# ISL6236A_DEMO.net
KiCad netlist of a schematic drawn in Altium Designer
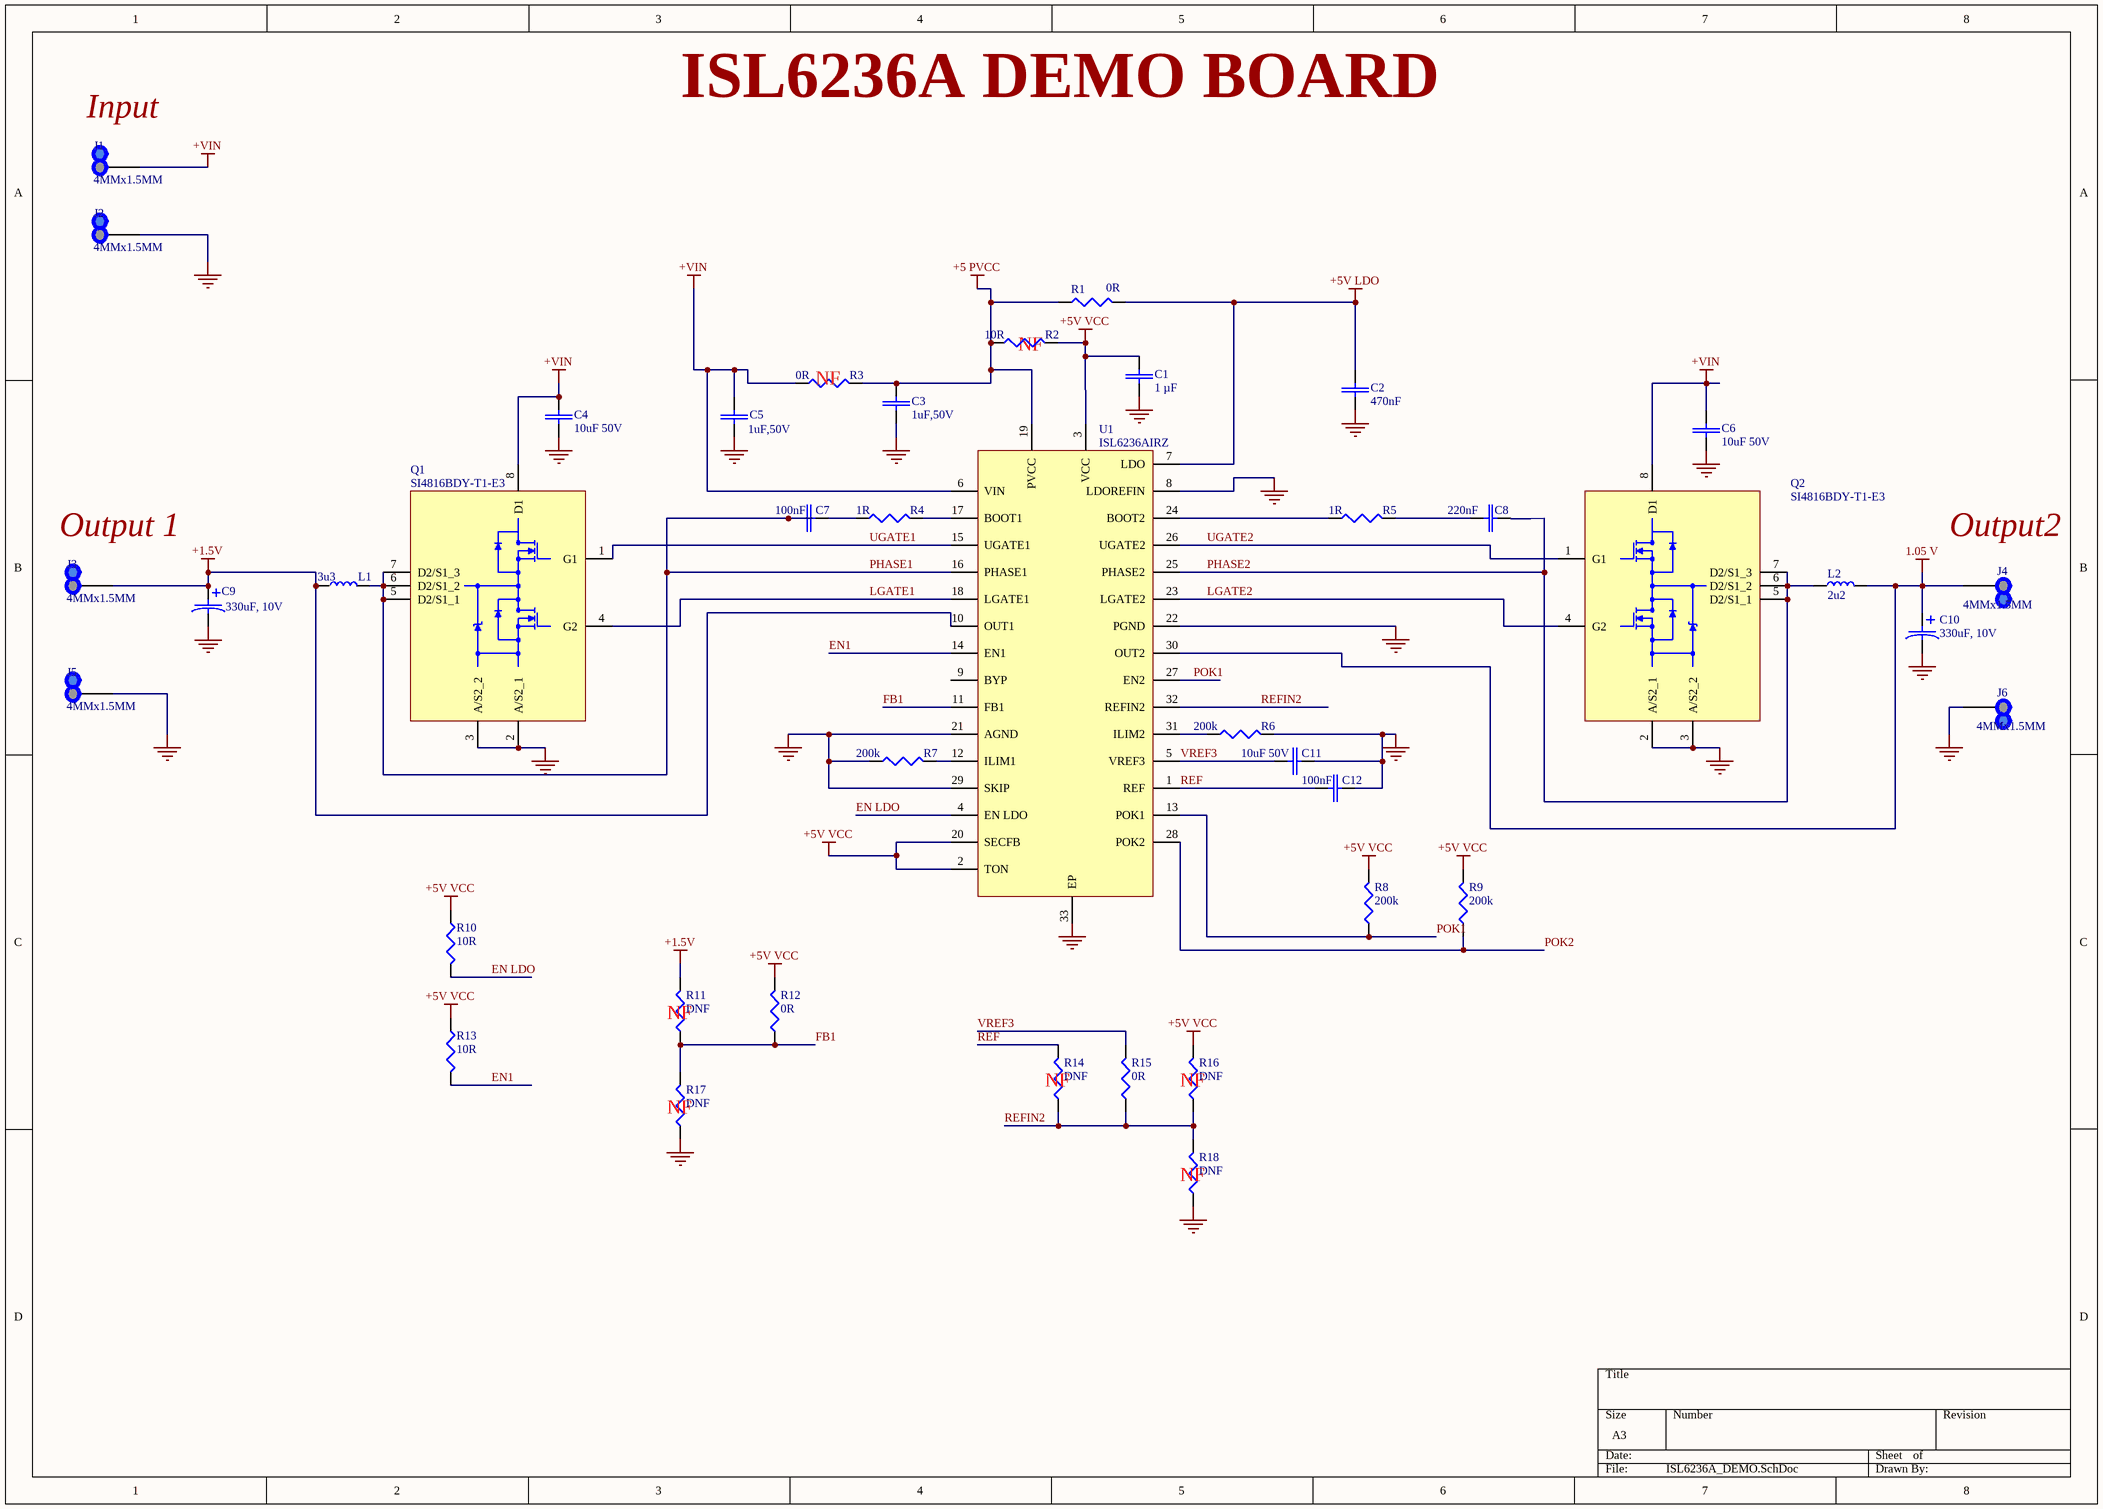
[diagram p0: ISL6236A_DEMO.SchDoc]

(export (version "E")
  (design (tool "Eeschema 10.0.6"))
  (components
    (comp (ref "C1")
      (value "1 µF")
      (footprint "C0805")
      (fields
        (field (name "TOLERANCE") "10%")
        (field (name "VOLTAGE") "25V")
        (field (name "MANUFACTURER") "Kyocera AVX")
      )
      (libsource (lib "ISL6236A_DEMO") (part "08053D105KAT2A"))
    )
    (comp (ref "C2")
      (value "470nF")
      (footprint "C1206")
      (description "Cap Ceramic 4.7uF 10V X5R 10% SMD 1206 85C T/R")
      (fields (field (name "TOLERANCE") "10%") (field (name "MANUFACTURER") "Taiyo Yuden"))
      (libsource (lib "ISL6236A_DEMO") (part "LMK316BJ475KD-T"))
    )
    (comp (ref "C3")
      (value "1uF,50V")
      (footprint "C0805")
      (fields
        (field (name "TOLERANCE") "10%")
        (field (name "MANUFACTURER") "TDK")
        (field (name "MANUFACTURER PART NUMBER") "C2012X7R1H105K125AB")
      )
      (libsource (lib "ISL6236A_DEMO") (part "C2012X7R1H105K125AB"))
    )
    (comp (ref "C4")
      (value "10uF 50V")
      (footprint "C1210")
      (description "CAP CER 10UF 50V X5R 1210")
      (fields (field (name "TOLERANCE") "20%") (field (name "MANUFACTURER") "Taiyo Yuden"))
      (libsource (lib "ISL6236A_DEMO") (part "UMK325BJ106MMHP"))
    )
    (comp (ref "C5")
      (value "1uF,50V")
      (footprint "C0805")
      (fields
        (field (name "TOLERANCE") "10%")
        (field (name "MANUFACTURER") "TDK")
        (field (name "MANUFACTURER PART NUMBER") "C2012X7R1H105K125AB")
      )
      (libsource (lib "ISL6236A_DEMO") (part "C2012X7R1H105K125AB"))
    )
    (comp (ref "C6")
      (value "10uF 50V")
      (footprint "C1210")
      (description "CAP CER 10UF 50V X5R 1210")
      (fields (field (name "TOLERANCE") "20%") (field (name "MANUFACTURER") "Taiyo Yuden"))
      (libsource (lib "ISL6236A_DEMO") (part "UMK325BJ106MMHP"))
    )
    (comp (ref "C7")
      (value "100nF")
      (footprint "C0805")
      (fields
        (field (name "TOLERANCE") "10%")
        (field (name "VOLTAGE") "50V")
        (field (name "MANUFACTURER") "Kyocera AVX")
      )
      (libsource (lib "ISL6236A_DEMO") (part "08055C104KAT4A"))
    )
    (comp (ref "C8")
      (value "220nF")
      (footprint "C0805")
      (description "TAIYO YUDEN - UMK212B7224KG-T - CERAMIC CAPACITOR 0.22UF, 50V, X7R, 10%, 0805, FULL REEL")
      (fields (field (name "TOLERANCE") "10%") (field (name "VOLTAGE") "50V"))
      (libsource (lib "ISL6236A_DEMO") (part "UMK212B7224KG-T"))
    )
    (comp (ref "C9")
      (value "330uF, 10V")
      (footprint "C7343-43")
      (description "Tantalum Capacitors - Polymer SMD 330uF 10volts 20%")
      (fields (field (name "TOLERANCE") "20%") (field (name "VOLTAGE") "10V"))
      (libsource (lib "ISL6236A_DEMO") (part "T530X337M010ATE004"))
    )
    (comp (ref "C10")
      (value "330uF, 10V")
      (footprint "C7343-43")
      (description "Tantalum Capacitors - Polymer SMD 330uF 10volts 20%")
      (fields (field (name "TOLERANCE") "20%") (field (name "VOLTAGE") "10V"))
      (libsource (lib "ISL6236A_DEMO") (part "T530X337M010ATE004"))
    )
    (comp (ref "C11")
      (value "10uF 50V")
      (footprint "C1210")
      (description "CAP CER 10UF 50V X5R 1210")
      (fields (field (name "TOLERANCE") "20%") (field (name "MANUFACTURER") "Taiyo Yuden"))
      (libsource (lib "ISL6236A_DEMO") (part "UMK325BJ106MMHP"))
    )
    (comp (ref "C12")
      (value "100nF")
      (footprint "C0805")
      (fields
        (field (name "TOLERANCE") "10%")
        (field (name "VOLTAGE") "50V")
        (field (name "MANUFACTURER") "Kyocera AVX")
      )
      (libsource (lib "ISL6236A_DEMO") (part "08055C104KAT4A"))
    )
    (comp (ref "J1")
      (value "4MMx1.5MM")
      (footprint "PAD_WITH_HOLE_4MM_1.5MM")
      (description "Pad with a hole 4mm x 1.5mm")
      (libsource (lib "ISL6236A_DEMO") (part "PAD_WITH_HOLE_4MMx1.5MM"))
    )
    (comp (ref "J2")
      (value "4MMx1.5MM")
      (footprint "PAD_WITH_HOLE_4MM_1.5MM")
      (description "Pad with a hole 4mm x 1.5mm")
      (libsource (lib "ISL6236A_DEMO") (part "PAD_WITH_HOLE_4MMx1.5MM"))
    )
    (comp (ref "J3")
      (value "4MMx1.5MM")
      (footprint "PAD_WITH_HOLE_4MM_1.5MM")
      (description "Pad with a hole 4mm x 1.5mm")
      (libsource (lib "ISL6236A_DEMO") (part "PAD_WITH_HOLE_4MMx1.5MM"))
    )
    (comp (ref "J4")
      (value "4MMx1.5MM")
      (footprint "PAD_WITH_HOLE_4MM_1.5MM")
      (description "Pad with a hole 4mm x 1.5mm")
      (libsource (lib "") (part "PAD_WITH_HOLE_4MMx1.5MM_1"))
    )
    (comp (ref "J5")
      (value "4MMx1.5MM")
      (footprint "PAD_WITH_HOLE_4MM_1.5MM")
      (description "Pad with a hole 4mm x 1.5mm")
      (libsource (lib "ISL6236A_DEMO") (part "PAD_WITH_HOLE_4MMx1.5MM"))
    )
    (comp (ref "J6")
      (value "4MMx1.5MM")
      (footprint "PAD_WITH_HOLE_4MM_1.5MM")
      (description "Pad with a hole 4mm x 1.5mm")
      (libsource (lib "") (part "PAD_WITH_HOLE_4MMx1.5MM_1"))
    )
    (comp (ref "L1")
      (value "3u3")
      (footprint "Inductor 744313330")
      (description "WURTH ELEKTRONIK - 744313330 - INDUCTOR, HIGH CURRENT 2.45UH, SMD")
      (fields (field (name "TOLERANCE") "20%") (field (name "MANUFACTURER") "Wurth Electronics"))
      (libsource (lib "ISL6236A_DEMO") (part "744313330"))
    )
    (comp (ref "L2")
      (value "2u2")
      (footprint "Inductor PCC-M1040M-LP")
      (description "Power Choke Shielded Wirewound 2.2uH 20% 100KHz Metal 14.8A 0.00748Ohm DCR Automotive T/R")
      (fields
        (field (name "MANUFACTURER") "Panasonic")
        (field (name "MANUFACTURER PART NUMBER") "ETQP4M2R2KVC")
      )
      (libsource (lib "ISL6236A_DEMO") (part "ETQP4M2R2KVC"))
    )
    (comp (ref "Q1")
      (value "SI4816BDY-T1-E3")
      (footprint "SO-8")
      (description "MOSFET 2N-CH 30V 5.8A 8-SOIC")
      (fields (field (name "MANUFACTURER") "Vishay Siliconix"))
      (libsource (lib "ISL6236A_DEMO") (part "SI4816BDY-T1-E3"))
    )
    (comp (ref "Q2")
      (value "SI4816BDY-T1-E3")
      (footprint "SO-8")
      (description "MOSFET 2N-CH 30V 5.8A 8-SOIC")
      (fields (field (name "MANUFACTURER") "Vishay Siliconix"))
      (libsource (lib "ISL6236A_DEMO") (part "SI4816BDY-T1-E3"))
    )
    (comp (ref "R1")
      (value "0R")
      (footprint "R0805")
      (fields
        (field (name "MANUFACTURER") "Stackpole Electronics")
        (field (name "MANUFACTURER PART NUMBER") "RMCF0805ZT0R00")
      )
      (libsource (lib "ISL6236A_DEMO") (part "RMCF0805ZT0R00"))
    )
    (comp (ref "R2")
      (value "10R")
      (footprint "R0805")
      (description "Res Thin Film 0805 10 Ohm 0.05% 1/10W 10ppm/C Molded SMD SMD Paper T/R")
      (fields (field (name "TOLERANCE") "0.05%") (field (name "MANUFACTURER") "Stackpole Electronics"))
      (libsource (lib "ISL6236A_DEMO") (part "RNCF0805AKT10R0"))
    )
    (comp (ref "R3")
      (value "0R")
      (footprint "R0805")
      (fields
        (field (name "MANUFACTURER") "Stackpole Electronics")
        (field (name "MANUFACTURER PART NUMBER") "RMCF0805ZT0R00")
      )
      (libsource (lib "ISL6236A_DEMO") (part "RMCF0805ZT0R00"))
    )
    (comp (ref "R4")
      (value "1R")
      (footprint "C0805")
      (fields
        (field (name "TOLERANCE") "1%")
        (field (name "MANUFACTURER") "Panasonic")
        (field (name "MANUFACTURER PART NUMBER") "ERJ-6RQF1R0V")
      )
      (libsource (lib "ISL6236A_DEMO") (part "ERJ-6RQF1R0V"))
    )
    (comp (ref "R5")
      (value "1R")
      (footprint "C0805")
      (fields
        (field (name "TOLERANCE") "1%")
        (field (name "MANUFACTURER") "Panasonic")
        (field (name "MANUFACTURER PART NUMBER") "ERJ-6RQF1R0V")
      )
      (libsource (lib "ISL6236A_DEMO") (part "ERJ-6RQF1R0V"))
    )
    (comp (ref "R6")
      (value "200k")
      (footprint "R0805")
      (fields
        (field (name "TOLERANCE") "1%")
        (field (name "MANUFACTURER") "Panasonic")
        (field (name "MANUFACTURER PART NUMBER") "ERJ-6ENF2003V")
      )
      (libsource (lib "ISL6236A_DEMO") (part "ERJ-6ENF2003V"))
    )
    (comp (ref "R7")
      (value "200k")
      (footprint "R0805")
      (fields
        (field (name "TOLERANCE") "1%")
        (field (name "MANUFACTURER") "Panasonic")
        (field (name "MANUFACTURER PART NUMBER") "ERJ-6ENF2003V")
      )
      (libsource (lib "ISL6236A_DEMO") (part "ERJ-6ENF2003V"))
    )
    (comp (ref "R8")
      (value "200k")
      (footprint "R0805")
      (fields
        (field (name "TOLERANCE") "1%")
        (field (name "MANUFACTURER") "Panasonic")
        (field (name "MANUFACTURER PART NUMBER") "ERJ-6ENF2003V")
      )
      (libsource (lib "ISL6236A_DEMO") (part "ERJ-6ENF2003V"))
    )
    (comp (ref "R9")
      (value "200k")
      (footprint "R0805")
      (fields
        (field (name "TOLERANCE") "1%")
        (field (name "MANUFACTURER") "Panasonic")
        (field (name "MANUFACTURER PART NUMBER") "ERJ-6ENF2003V")
      )
      (libsource (lib "ISL6236A_DEMO") (part "ERJ-6ENF2003V"))
    )
    (comp (ref "R10")
      (value "10R")
      (footprint "R0805")
      (description "Res Thin Film 0805 10 Ohm 0.05% 1/10W 10ppm/C Molded SMD SMD Paper T/R")
      (fields (field (name "TOLERANCE") "0.05%") (field (name "MANUFACTURER") "Stackpole Electronics"))
      (libsource (lib "ISL6236A_DEMO") (part "RNCF0805AKT10R0"))
    )
    (comp (ref "R11") (value "DNF") (footprint "R0805") (libsource (lib "ISL6236A_DEMO") (part "RES")))
    (comp (ref "R12")
      (value "0R")
      (footprint "R0805")
      (fields
        (field (name "MANUFACTURER") "Stackpole Electronics")
        (field (name "MANUFACTURER PART NUMBER") "RMCF0805ZT0R00")
      )
      (libsource (lib "ISL6236A_DEMO") (part "RMCF0805ZT0R00"))
    )
    (comp (ref "R13")
      (value "10R")
      (footprint "R0805")
      (description "Res Thin Film 0805 10 Ohm 0.05% 1/10W 10ppm/C Molded SMD SMD Paper T/R")
      (fields (field (name "TOLERANCE") "0.05%") (field (name "MANUFACTURER") "Stackpole Electronics"))
      (libsource (lib "ISL6236A_DEMO") (part "RNCF0805AKT10R0"))
    )
    (comp (ref "R14") (value "DNF") (footprint "R0805") (libsource (lib "ISL6236A_DEMO") (part "RES")))
    (comp (ref "R15")
      (value "0R")
      (footprint "R0805")
      (fields
        (field (name "MANUFACTURER") "Stackpole Electronics")
        (field (name "MANUFACTURER PART NUMBER") "RMCF0805ZT0R00")
      )
      (libsource (lib "ISL6236A_DEMO") (part "RMCF0805ZT0R00"))
    )
    (comp (ref "R16") (value "DNF") (footprint "R0805") (libsource (lib "ISL6236A_DEMO") (part "RES")))
    (comp (ref "R17") (value "DNF") (footprint "R0805") (libsource (lib "ISL6236A_DEMO") (part "RES")))
    (comp (ref "R18") (value "DNF") (footprint "R0805") (libsource (lib "ISL6236A_DEMO") (part "RES")))
    (comp (ref "U1")
      (value "ISL6236AIRZ")
      (footprint "ISL5236A L32.5X5B - duplicate")
      (description "IC MAIN PWR CTRLR QUAD 32-QFN")
      (fields (field (name "MANUFACTURER") "Intersil"))
      (libsource (lib "ISL6236A_DEMO") (part "ISL6236AIRZ"))
    )
  )
  (nets
    (net (code "1") (name "+1.5V") (class "Default")
      (node (ref "C9") (pin "1") (pinfunction "1_1") (pintype "passive"))
      (node (ref "J3") (pin "1") (pinfunction "1_1") (pintype "passive"))
      (node (ref "L1") (pin "1") (pinfunction "1_1") (pintype "passive"))
      (node (ref "R11") (pin "2") (pinfunction "2_2") (pintype "passive"))
      (node (ref "U1") (pin "10") (pinfunction "OUT1_10") (pintype "passive"))
    )
    (net (code "2") (name "+5 PVCC") (class "Default")
      (node (ref "C3") (pin "2") (pinfunction "2_2") (pintype "passive"))
      (node (ref "R1") (pin "1") (pinfunction "1_1") (pintype "passive"))
      (node (ref "R2") (pin "1") (pinfunction "1_1") (pintype "passive"))
      (node (ref "R3") (pin "2") (pinfunction "2_2") (pintype "passive"))
      (node (ref "U1") (pin "19") (pinfunction "PVCC_19") (pintype "passive"))
    )
    (net (code "3") (name "+5V LDO") (class "Default")
      (node (ref "C2") (pin "2") (pinfunction "2_2") (pintype "passive"))
      (node (ref "R1") (pin "2") (pinfunction "2_2") (pintype "passive"))
      (node (ref "U1") (pin "7") (pinfunction "LDO_7") (pintype "passive"))
    )
    (net (code "4") (name "+5V VCC") (class "Default")
      (node (ref "C1") (pin "2") (pinfunction "2_2") (pintype "passive"))
      (node (ref "R10") (pin "1") (pinfunction "1_1") (pintype "passive"))
      (node (ref "R12") (pin "2") (pinfunction "2_2") (pintype "passive"))
      (node (ref "R13") (pin "1") (pinfunction "1_1") (pintype "passive"))
      (node (ref "R16") (pin "2") (pinfunction "2_2") (pintype "passive"))
      (node (ref "R2") (pin "2") (pinfunction "2_2") (pintype "passive"))
      (node (ref "R8") (pin "2") (pinfunction "2_2") (pintype "passive"))
      (node (ref "R9") (pin "2") (pinfunction "2_2") (pintype "passive"))
      (node (ref "U1") (pin "2") (pinfunction "TON_2") (pintype "passive"))
      (node (ref "U1") (pin "20") (pinfunction "SECFB_20") (pintype "passive"))
      (node (ref "U1") (pin "3") (pinfunction "VCC_3") (pintype "passive"))
    )
    (net (code "5") (name "+VIN") (class "Default")
      (node (ref "C4") (pin "2") (pinfunction "2_2") (pintype "passive"))
      (node (ref "C5") (pin "2") (pinfunction "2_2") (pintype "passive"))
      (node (ref "C6") (pin "2") (pinfunction "2_2") (pintype "passive"))
      (node (ref "J1") (pin "1") (pinfunction "1_1") (pintype "passive"))
      (node (ref "Q1") (pin "8") (pinfunction "D1_8") (pintype "passive"))
      (node (ref "Q2") (pin "8") (pinfunction "D1_8") (pintype "passive"))
      (node (ref "R3") (pin "1") (pinfunction "1_1") (pintype "passive"))
      (node (ref "U1") (pin "6") (pinfunction "VIN_6") (pintype "passive"))
    )
    (net (code "6") (name "/EN LDO") (class "Default")
      (node (ref "R10") (pin "2") (pinfunction "2_2") (pintype "passive"))
      (node (ref "U1") (pin "4") (pinfunction "EN_LDO_4") (pintype "passive"))
    )
    (net (code "7") (name "/EN1") (class "Default")
      (node (ref "R13") (pin "2") (pinfunction "2_2") (pintype "passive"))
      (node (ref "U1") (pin "14") (pinfunction "EN1_14") (pintype "passive"))
    )
    (net (code "8") (name "/FB1") (class "Default")
      (node (ref "R11") (pin "1") (pinfunction "1_1") (pintype "passive"))
      (node (ref "R12") (pin "1") (pinfunction "1_1") (pintype "passive"))
      (node (ref "R17") (pin "2") (pinfunction "2_2") (pintype "passive"))
      (node (ref "U1") (pin "11") (pinfunction "FB1_11") (pintype "passive"))
    )
    (net (code "9") (name "/LGATE1") (class "Default")
      (node (ref "Q1") (pin "4") (pinfunction "G2_4") (pintype "passive"))
      (node (ref "U1") (pin "18") (pinfunction "LGATE1_18") (pintype "passive"))
    )
    (net (code "10") (name "/LGATE2") (class "Default")
      (node (ref "Q2") (pin "4") (pinfunction "G2_4") (pintype "passive"))
      (node (ref "U1") (pin "23") (pinfunction "LGATE2_23") (pintype "passive"))
    )
    (net (code "11") (name "/PHASE1") (class "Default")
      (node (ref "C7") (pin "1") (pinfunction "1_1") (pintype "passive"))
      (node (ref "L1") (pin "2") (pinfunction "2_2") (pintype "passive"))
      (node (ref "Q1") (pin "5") (pinfunction "D2/S1_1_5") (pintype "passive"))
      (node (ref "Q1") (pin "6") (pinfunction "D2/S1_2_6") (pintype "passive"))
      (node (ref "Q1") (pin "7") (pinfunction "D2/S1_3_7") (pintype "passive"))
      (node (ref "U1") (pin "16") (pinfunction "PHASE1_16") (pintype "passive"))
    )
    (net (code "12") (name "/PHASE2") (class "Default")
      (node (ref "C8") (pin "2") (pinfunction "2_2") (pintype "passive"))
      (node (ref "L2") (pin "1") (pinfunction "1_1") (pintype "passive"))
      (node (ref "Q2") (pin "5") (pinfunction "D2/S1_1_5") (pintype "passive"))
      (node (ref "Q2") (pin "6") (pinfunction "D2/S1_2_6") (pintype "passive"))
      (node (ref "Q2") (pin "7") (pinfunction "D2/S1_3_7") (pintype "passive"))
      (node (ref "U1") (pin "25") (pinfunction "PHASE2_25") (pintype "passive"))
    )
    (net (code "13") (name "/POK1") (class "Default")
      (node (ref "R8") (pin "1") (pinfunction "1_1") (pintype "passive"))
      (node (ref "U1") (pin "13") (pinfunction "POK1_13") (pintype "passive"))
      (node (ref "U1") (pin "27") (pinfunction "EN2_27") (pintype "passive"))
    )
    (net (code "14") (name "/POK2") (class "Default")
      (node (ref "R9") (pin "1") (pinfunction "1_1") (pintype "passive"))
      (node (ref "U1") (pin "28") (pinfunction "POK2_28") (pintype "passive"))
    )
    (net (code "15") (name "/REF") (class "Default")
      (node (ref "C12") (pin "1") (pinfunction "1_1") (pintype "passive"))
      (node (ref "R14") (pin "2") (pinfunction "2_2") (pintype "passive"))
      (node (ref "U1") (pin "1") (pinfunction "REF_1") (pintype "passive"))
    )
    (net (code "16") (name "/REFIN2") (class "Default")
      (node (ref "R14") (pin "1") (pinfunction "1_1") (pintype "passive"))
      (node (ref "R15") (pin "1") (pinfunction "1_1") (pintype "passive"))
      (node (ref "R16") (pin "1") (pinfunction "1_1") (pintype "passive"))
      (node (ref "R18") (pin "2") (pinfunction "2_2") (pintype "passive"))
      (node (ref "U1") (pin "32") (pinfunction "REFIN2_32") (pintype "passive"))
    )
    (net (code "17") (name "/UGATE1") (class "Default")
      (node (ref "Q1") (pin "1") (pinfunction "G1_1") (pintype "passive"))
      (node (ref "U1") (pin "15") (pinfunction "UGATE1_15") (pintype "passive"))
    )
    (net (code "18") (name "/UGATE2") (class "Default")
      (node (ref "Q2") (pin "1") (pinfunction "G1_1") (pintype "passive"))
      (node (ref "U1") (pin "26") (pinfunction "UGATE2_26") (pintype "passive"))
    )
    (net (code "19") (name "/VREF3") (class "Default")
      (node (ref "C11") (pin "1") (pinfunction "1_1") (pintype "passive"))
      (node (ref "R15") (pin "2") (pinfunction "2_2") (pintype "passive"))
      (node (ref "U1") (pin "5") (pinfunction "VREF3_5") (pintype "passive"))
    )
    (net (code "20") (name "1.05 V") (class "Default")
      (node (ref "C10") (pin "1") (pinfunction "1_1") (pintype "passive"))
      (node (ref "J4") (pin "1") (pinfunction "1_1") (pintype "passive"))
      (node (ref "L2") (pin "2") (pinfunction "2_2") (pintype "passive"))
      (node (ref "U1") (pin "30") (pinfunction "OUT2_30") (pintype "passive"))
    )
    (net (code "21") (name "GND") (class "Default")
      (node (ref "C1") (pin "1") (pinfunction "1_1") (pintype "passive"))
      (node (ref "C10") (pin "2") (pinfunction "2_2") (pintype "passive"))
      (node (ref "C11") (pin "2") (pinfunction "2_2") (pintype "passive"))
      (node (ref "C12") (pin "2") (pinfunction "2_2") (pintype "passive"))
      (node (ref "C2") (pin "1") (pinfunction "1_1") (pintype "passive"))
      (node (ref "C3") (pin "1") (pinfunction "1_1") (pintype "passive"))
      (node (ref "C4") (pin "1") (pinfunction "1_1") (pintype "passive"))
      (node (ref "C5") (pin "1") (pinfunction "1_1") (pintype "passive"))
      (node (ref "C6") (pin "1") (pinfunction "1_1") (pintype "passive"))
      (node (ref "C9") (pin "2") (pinfunction "2_2") (pintype "passive"))
      (node (ref "J2") (pin "1") (pinfunction "1_1") (pintype "passive"))
      (node (ref "J5") (pin "1") (pinfunction "1_1") (pintype "passive"))
      (node (ref "J6") (pin "1") (pinfunction "1_1") (pintype "passive"))
      (node (ref "Q1") (pin "2") (pinfunction "A/S2_1_2") (pintype "passive"))
      (node (ref "Q1") (pin "3") (pinfunction "A/S2_2_3") (pintype "passive"))
      (node (ref "Q2") (pin "2") (pinfunction "A/S2_1_2") (pintype "passive"))
      (node (ref "Q2") (pin "3") (pinfunction "A/S2_2_3") (pintype "passive"))
      (node (ref "R17") (pin "1") (pinfunction "1_1") (pintype "passive"))
      (node (ref "R18") (pin "1") (pinfunction "1_1") (pintype "passive"))
      (node (ref "R6") (pin "2") (pinfunction "2_2") (pintype "passive"))
      (node (ref "R7") (pin "1") (pinfunction "1_1") (pintype "passive"))
      (node (ref "U1") (pin "21") (pinfunction "AGND_21") (pintype "passive"))
      (node (ref "U1") (pin "22") (pinfunction "PGND_22") (pintype "passive"))
      (node (ref "U1") (pin "29") (pinfunction "SKIP_29") (pintype "passive"))
      (node (ref "U1") (pin "33") (pinfunction "EP_33") (pintype "passive"))
      (node (ref "U1") (pin "8") (pinfunction "LDOREFIN_8") (pintype "passive"))
    )
    (net (code "22") (name "Net-(C7-Pad2)") (class "Default")
      (node (ref "C7") (pin "2") (pinfunction "2_2") (pintype "passive"))
      (node (ref "R4") (pin "1") (pinfunction "1_1") (pintype "passive"))
    )
    (net (code "23") (name "Net-(C8-Pad1)") (class "Default")
      (node (ref "C8") (pin "1") (pinfunction "1_1") (pintype "passive"))
      (node (ref "R5") (pin "2") (pinfunction "2_2") (pintype "passive"))
    )
    (net (code "24") (name "Net-(U1-BOOT1)") (class "Default")
      (node (ref "R4") (pin "2") (pinfunction "2_2") (pintype "passive"))
      (node (ref "U1") (pin "17") (pinfunction "BOOT1_17") (pintype "passive"))
    )
    (net (code "25") (name "Net-(U1-BOOT2)") (class "Default")
      (node (ref "R5") (pin "1") (pinfunction "1_1") (pintype "passive"))
      (node (ref "U1") (pin "24") (pinfunction "BOOT2_24") (pintype "passive"))
    )
    (net (code "26") (name "Net-(U1-ILIM1)") (class "Default")
      (node (ref "R7") (pin "2") (pinfunction "2_2") (pintype "passive"))
      (node (ref "U1") (pin "12") (pinfunction "ILIM1_12") (pintype "passive"))
    )
    (net (code "27") (name "Net-(U1-ILIM2)") (class "Default")
      (node (ref "R6") (pin "1") (pinfunction "1_1") (pintype "passive"))
      (node (ref "U1") (pin "31") (pinfunction "ILIM2_31") (pintype "passive"))
    )
    (net (code "28") (name "unconnected-(U1-BYP-Pad9)") (class "Default")
      (node (ref "U1") (pin "9") (pinfunction "BYP_9") (pintype "passive"))
    )
  )
)
